# Ball_Detection_v4.net
KiCad netlist of a schematic drawn in EAGLE
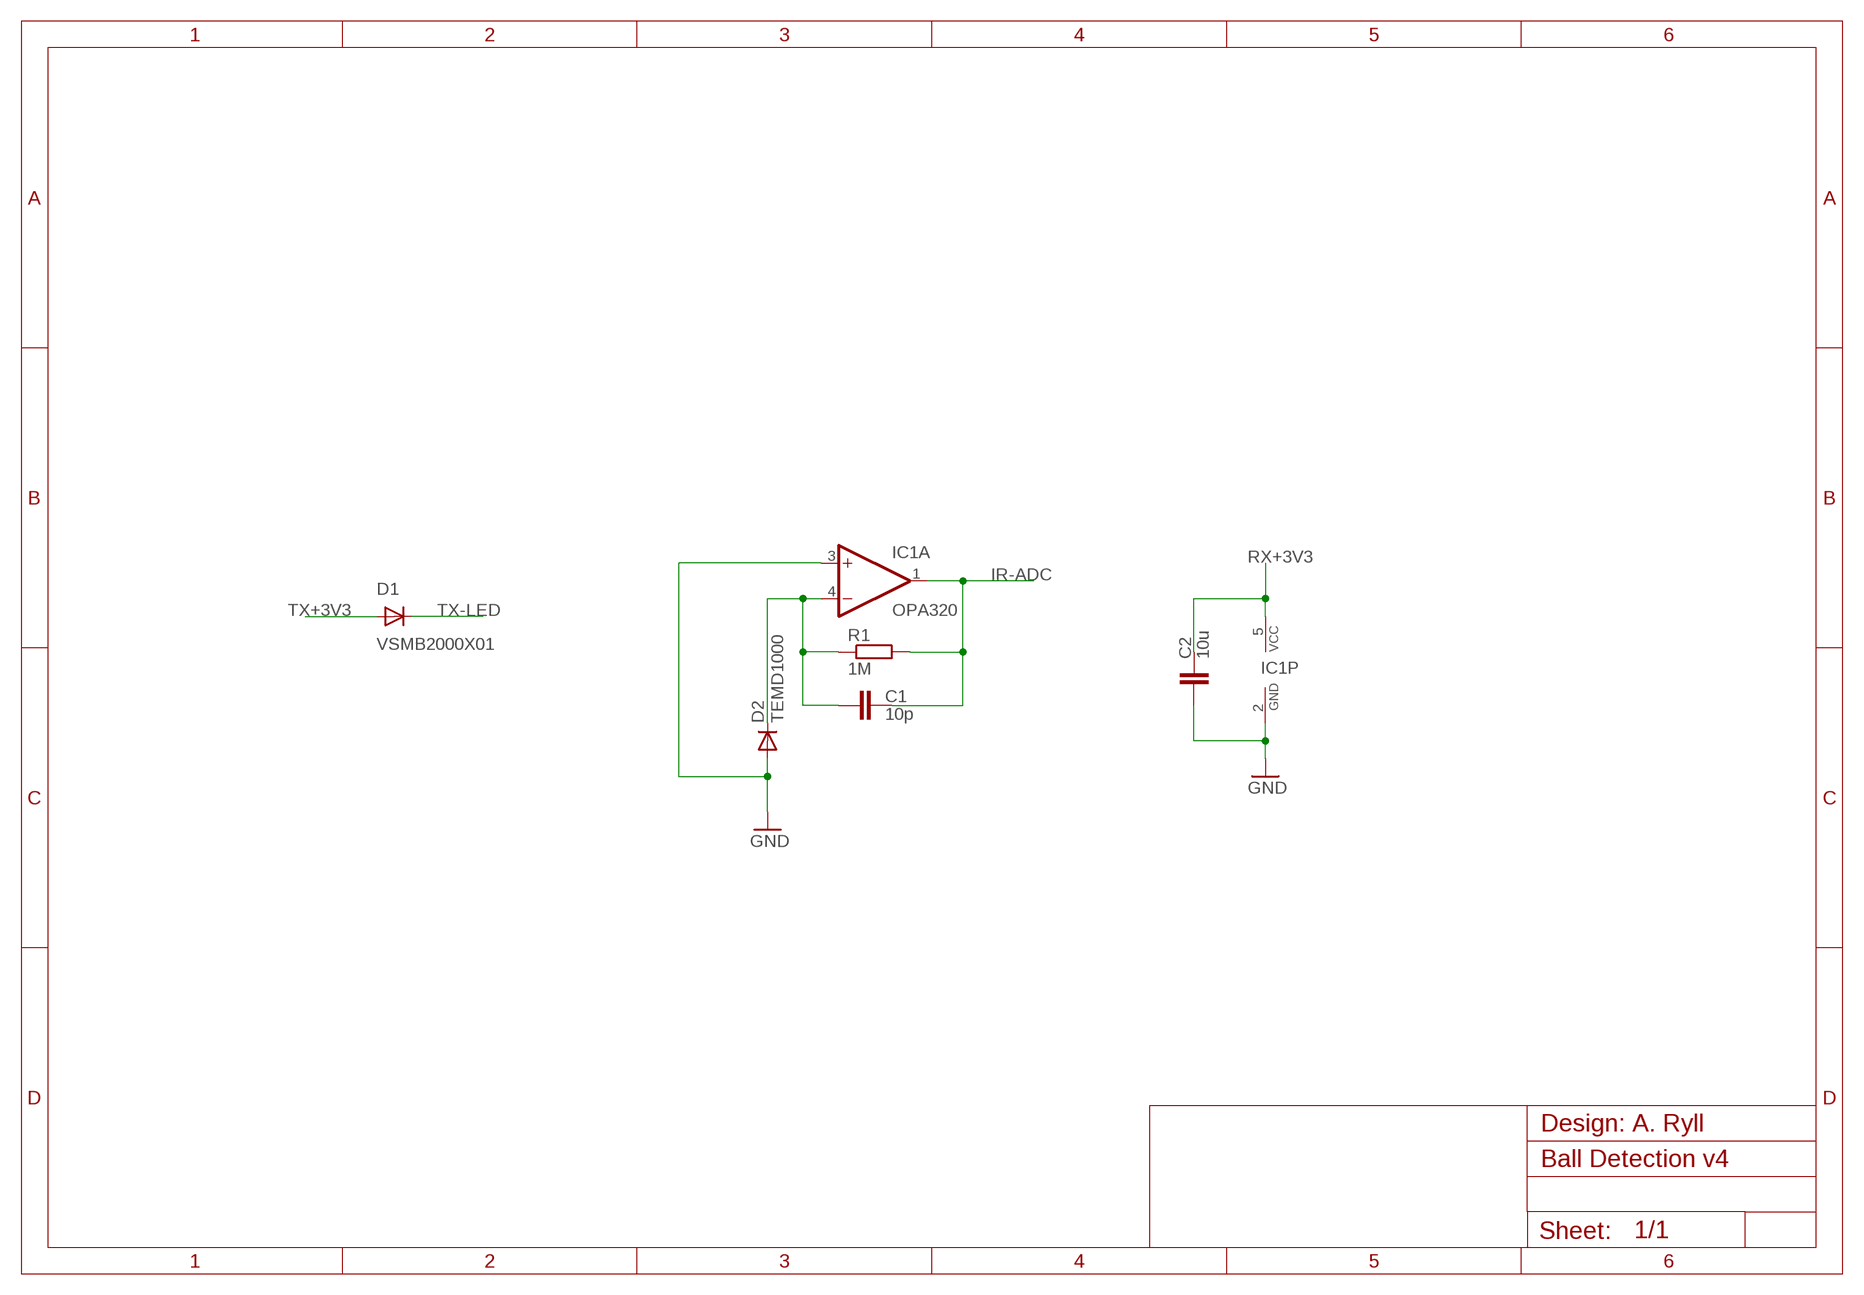
[diagram p0: schematic, sheet 1]

(export (version "E")
  (design (tool "Eeschema 10.0.6"))
  (components
    (comp (ref "C1")
      (value "10p")
      (footprint "eagle-import:C0603")
      (libsource (lib "eagle-import") (part "C-EUC0603"))
    )
    (comp (ref "C2")
      (value "10u")
      (footprint "eagle-import:C0603")
      (libsource (lib "eagle-import") (part "C-EUC0603"))
    )
    (comp (ref "D1")
      (value "VSMB2000X01")
      (footprint "eagle-import:LED-GULLR")
      (libsource (lib "eagle-import") (part "DIODE"))
    )
    (comp (ref "D2")
      (value "TEMD1000")
      (footprint "eagle-import:LED-GULLR")
      (libsource (lib "eagle-import") (part "DIODE"))
    )
    (comp (ref "IC1")
      (value "OPA320")
      (footprint "eagle-import:SOT23-5")
      (libsource (lib "eagle-import") (part "AD-OP1RT"))
    )
    (comp (ref "R1")
      (value "1M")
      (footprint "eagle-import:R0603")
      (libsource (lib "eagle-import") (part "R-EU_R0603"))
    )
  )
  (nets
    (net (code "1") (name "/IR-ADC") (class "Default")
      (node (ref "C1") (pin "2") (pinfunction "2_2") (pintype "passive"))
      (node (ref "IC1") (pin "1") (pinfunction "OUT_1") (pintype "output"))
      (node (ref "R1") (pin "2") (pinfunction "2_2") (pintype "passive"))
    )
    (net (code "2") (name "/RX+3V3") (class "Default")
      (node (ref "C2") (pin "2") (pinfunction "2_2") (pintype "passive"))
      (node (ref "IC1") (pin "5") (pinfunction "VCC_5") (pintype "power_in"))
    )
    (net (code "3") (name "/TX+3V3") (class "Default")
      (node (ref "D1") (pin "A") (pinfunction "A_A") (pintype "passive"))
    )
    (net (code "4") (name "/TX-LED") (class "Default")
      (node (ref "D1") (pin "C") (pinfunction "C_C") (pintype "passive"))
    )
    (net (code "5") (name "GND") (class "Default")
      (node (ref "C2") (pin "1") (pinfunction "1_1") (pintype "passive"))
      (node (ref "D2") (pin "A") (pinfunction "A_A") (pintype "passive"))
      (node (ref "IC1") (pin "2") (pinfunction "GND_2") (pintype "power_in"))
      (node (ref "IC1") (pin "3") (pinfunction "+IN_3") (pintype "input"))
    )
    (net (code "6") (name "Net-(IC1A--IN)") (class "Default")
      (node (ref "C1") (pin "1") (pinfunction "1_1") (pintype "passive"))
      (node (ref "D2") (pin "C") (pinfunction "C_C") (pintype "passive"))
      (node (ref "IC1") (pin "4") (pinfunction "-IN_4") (pintype "input"))
      (node (ref "R1") (pin "1") (pinfunction "1_1") (pintype "passive"))
    )
  )
)
